# batteryDivider.net
KiCad netlist of a schematic drawn in Altium Designer
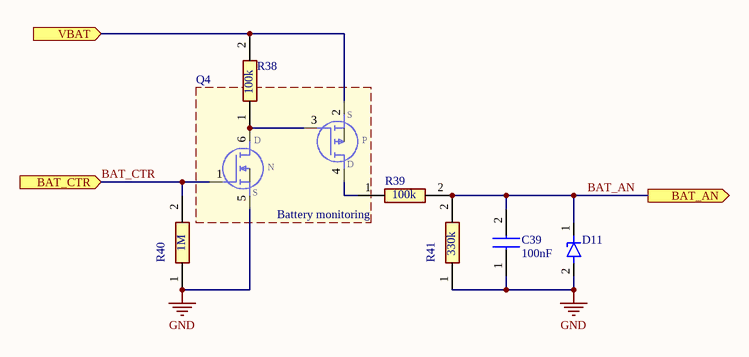
[diagram p0: batteryDivider.SchDoc]

(export (version "E")
  (design (tool "Eeschema 10.0.6"))
  (components
    (comp (ref "C39")
      (value "100nF")
      (footprint "SamacSys:CAPC1005X70N")
      (description "Capacitor")
      (fields
        (field (name "MANUFACTURER_PART_NUMBER") "GRM155R61A104KA01D")
        (field (name "MOUSER PART NUMBER") "81-GRM155R61A104KA01")
      )
      (libsource (lib "*") (part "GRM155R61A104KA01D"))
    )
    (comp (ref "D11")
      (value "SP3205-01ETG")
      (footprint "SamacSys:SP320501ETG")
      (description "Diode ESD (Uni-directional)")
      (fields (field (name "MOUSER PART NUMBER") "576-SP3205-01ETG"))
      (libsource (lib "SamacSys") (part "SP3205-01ETG"))
    )
    (comp (ref "Q4")
      (value "SI3552DV-T1-GE3")
      (footprint "SamacSys:SOT95P284X110-6N")
      (description "Transistor")
      (fields (field (name "MOUSER PART NUMBER") "781-SI3552DV-GE3"))
      (libsource (lib "SamacSys") (part "SI3552DV-T1-GE3"))
    )
    (comp (ref "R38")
      (value "100k")
      (footprint "SamacSys:RESC1005X35N")
      (description "Resistor")
      (fields
        (field (name "MANUFACTURER_PART_NUMBER") "RT0402FRE07100KL")
        (field (name "MOUSER PART NUMBER") "603-RT0402FRE07100KL")
      )
      (libsource (lib "*") (part "RT0402FRE07100KL"))
    )
    (comp (ref "R39")
      (value "100k")
      (footprint "SamacSys:RESC1005X40N")
      (description "Resistor")
      (fields (field (name "MANUFACTURER_PART_NUMBER") "RC0402BR-07100KL"))
      (libsource (lib "SamacSys") (part "RC0402BR-07100KL"))
    )
    (comp (ref "R40")
      (value "1M")
      (footprint "SamacSys:RESC1005X40N")
      (description "Resistor")
      (fields
        (field (name "MANUFACTURER_PART_NUMBER") "RC0402FR-071ML")
        (field (name "MOUSER PART NUMBER") "603-RC0402FR-071ML")
      )
      (libsource (lib "*") (part "RC0402FR-071ML"))
    )
    (comp (ref "R41")
      (value "330k")
      (footprint "SamacSys:RESC1005X40N")
      (description "Resistor")
      (fields (field (name "MANUFACTURER_PART_NUMBER") "RC0402BR-07330KL"))
      (libsource (lib "SamacSys") (part "RC0402BR-07330KL"))
    )
  )
  (nets
    (net (code "1") (name "/BAT_AN") (class "Default")
      (node (ref "C39") (pin "2") (pinfunction "2_2") (pintype "passive"))
      (node (ref "D11") (pin "1") (pinfunction "K_1") (pintype "passive"))
      (node (ref "R39") (pin "2") (pinfunction "2_2") (pintype "passive"))
      (node (ref "R41") (pin "2") (pinfunction "2_2") (pintype "passive"))
    )
    (net (code "2") (name "/BAT_CTR") (class "Default")
      (node (ref "Q4") (pin "1") (pinfunction "G1_1") (pintype "passive"))
      (node (ref "R40") (pin "2") (pinfunction "2_2") (pintype "passive"))
    )
    (net (code "3") (name "/VBAT") (class "Default")
      (node (ref "Q4") (pin "2") (pinfunction "S2_2") (pintype "passive"))
      (node (ref "R38") (pin "2") (pinfunction "2_2") (pintype "passive"))
    )
    (net (code "4") (name "GND") (class "Default")
      (node (ref "C39") (pin "1") (pinfunction "1_1") (pintype "passive"))
      (node (ref "D11") (pin "2") (pinfunction "A_2") (pintype "passive"))
      (node (ref "Q4") (pin "5") (pinfunction "S1_5") (pintype "passive"))
      (node (ref "R40") (pin "1") (pinfunction "1_1") (pintype "passive"))
      (node (ref "R41") (pin "1") (pinfunction "1_1") (pintype "passive"))
    )
    (net (code "5") (name "Net-(Q4-D1)") (class "Default")
      (node (ref "Q4") (pin "3") (pinfunction "G2_3") (pintype "passive"))
      (node (ref "Q4") (pin "6") (pinfunction "D1_6") (pintype "passive"))
      (node (ref "R38") (pin "1") (pinfunction "1_1") (pintype "passive"))
    )
    (net (code "6") (name "Net-(Q4-D2)") (class "Default")
      (node (ref "Q4") (pin "4") (pinfunction "D2_4") (pintype "passive"))
      (node (ref "R39") (pin "1") (pinfunction "1_1") (pintype "passive"))
    )
  )
)
